# ADC_4CH.net
KiCad netlist of a schematic drawn in Altium Designer
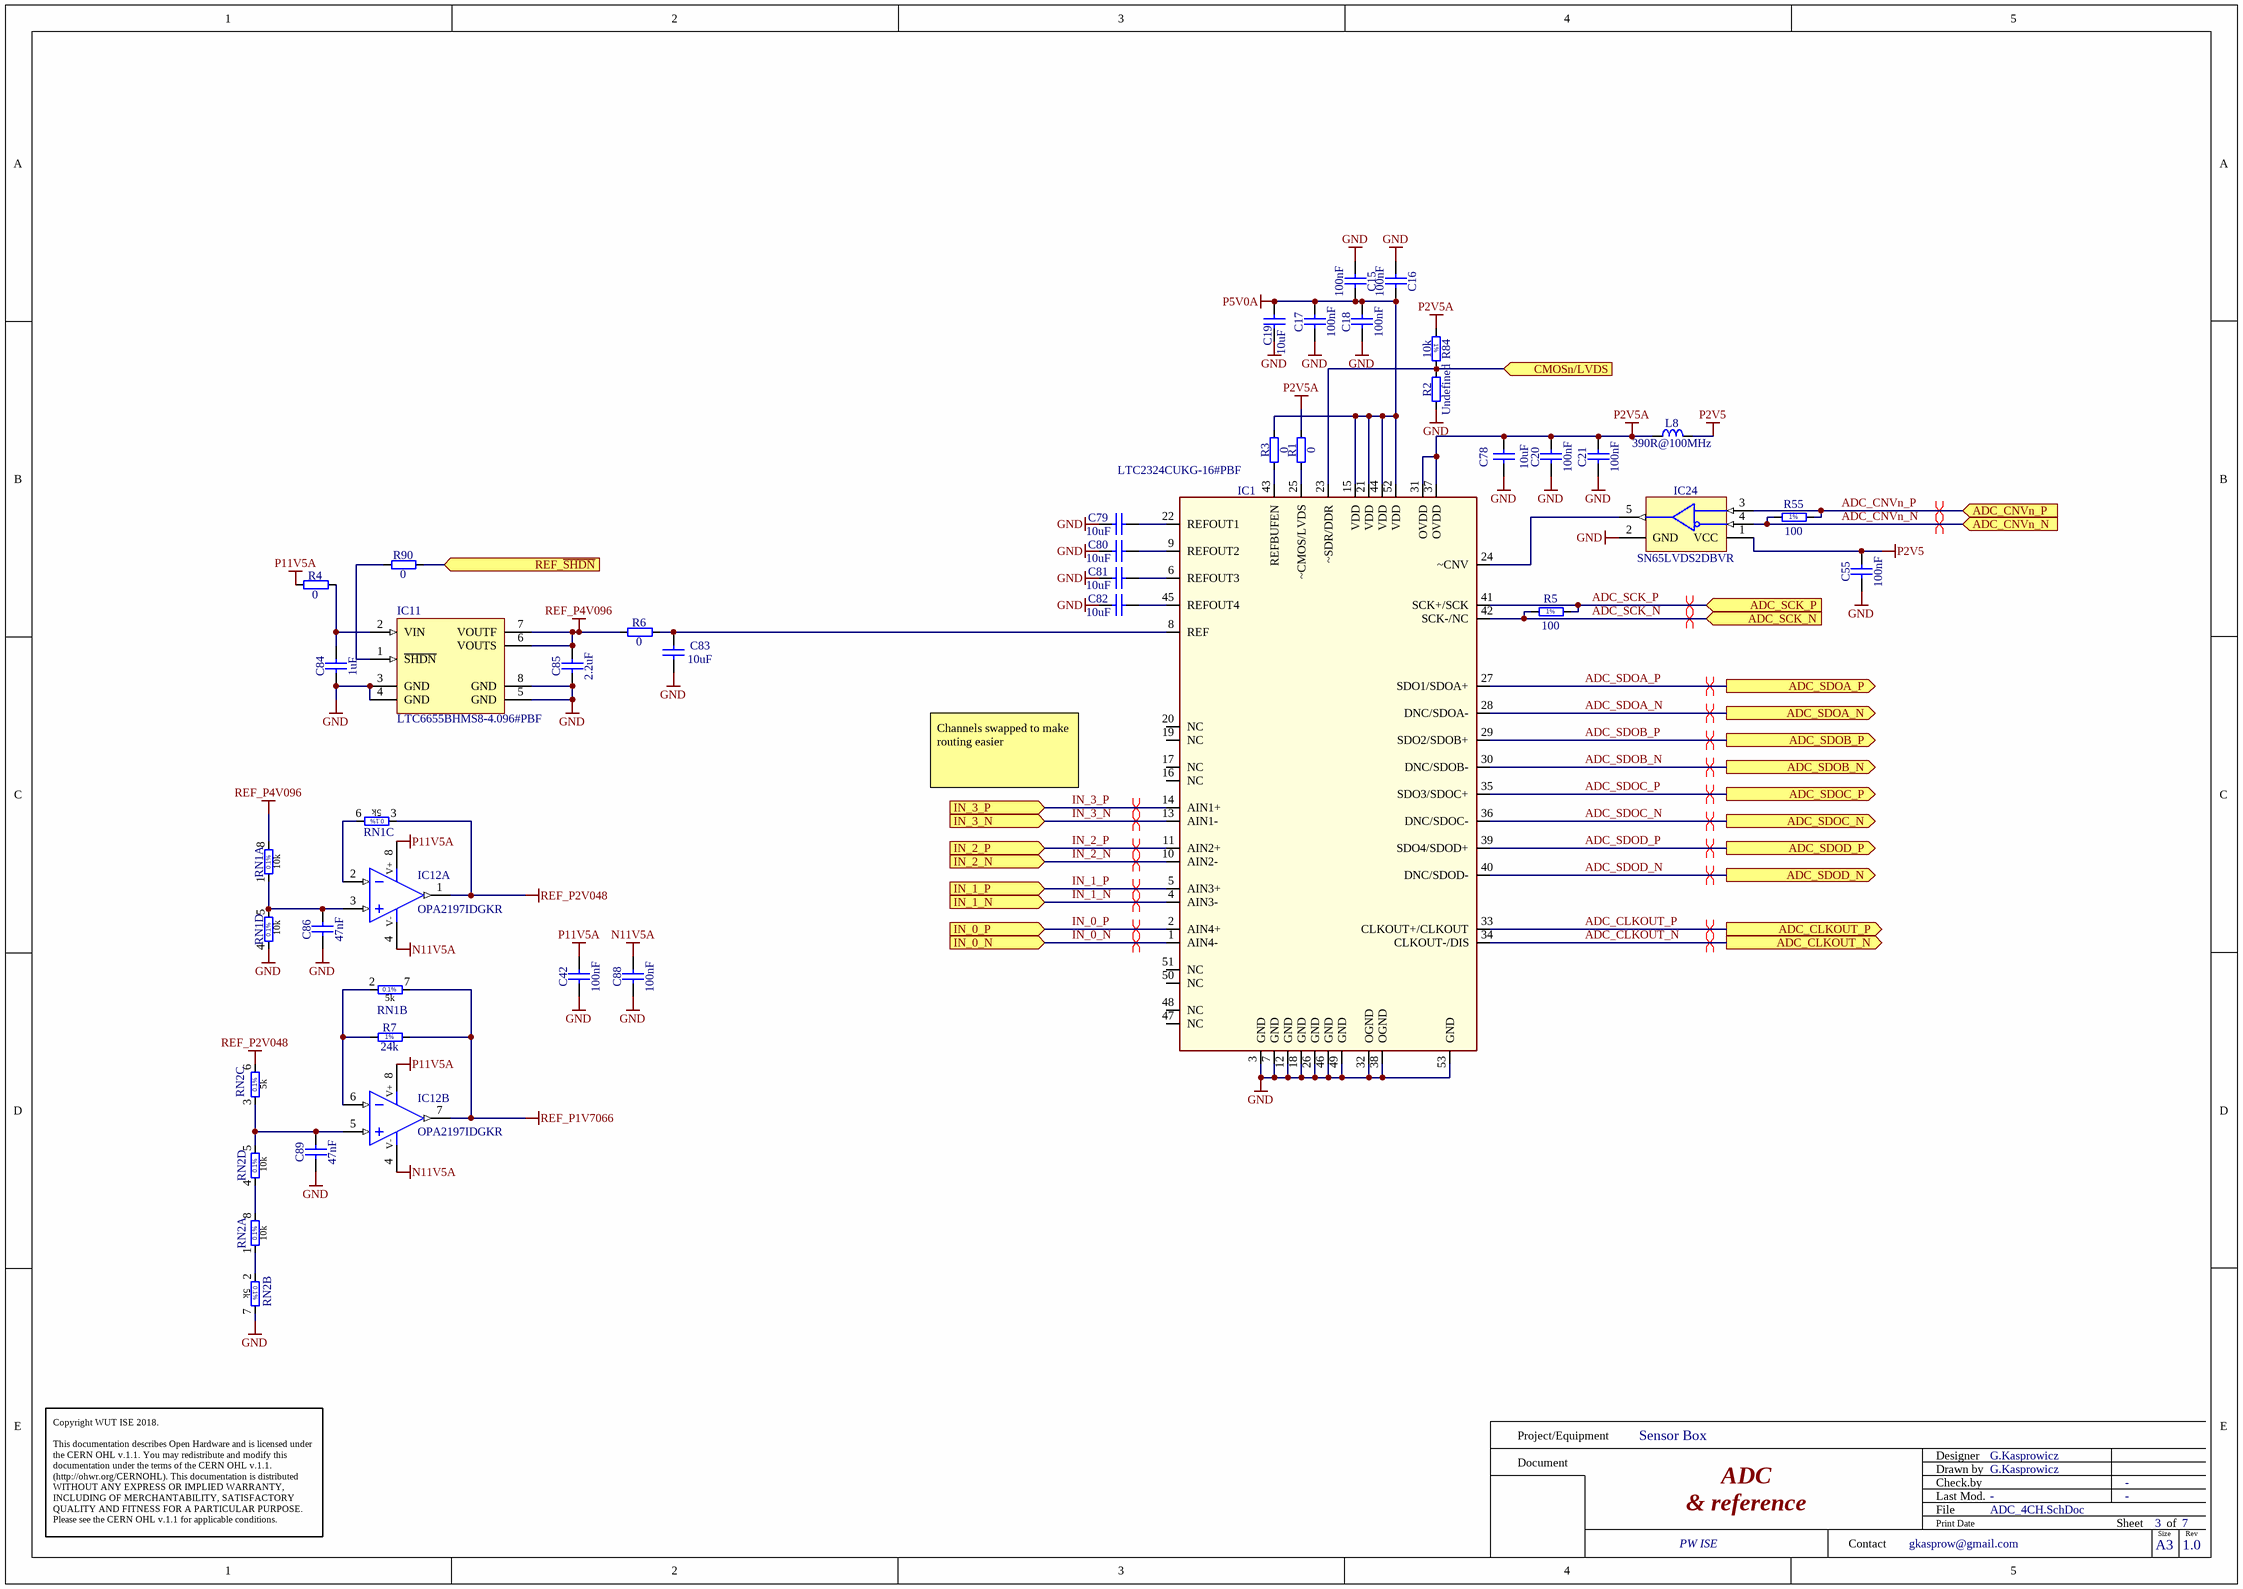
[diagram p0: ADC_4CH.SchDoc]

(export (version "E")
  (design (tool "Eeschema 10.0.6"))
  (components
    (comp (ref "C15")
      (value "100nF")
      (footprint "CAPC1608X87N")
      (description "Non-polarised capacitor")
      (fields
        (field (name "PART NUMBER") "CC0603_100NF_50V_10%_X7R")
        (field (name "VOLTAGE") "50V")
        (field (name "AUTHOR") "CERN DEM JLC")
      )
      (libsource (lib "Capacitors") (part "Capacitor - non polarized"))
    )
    (comp (ref "C16")
      (value "100nF")
      (footprint "CAPC1608X87N")
      (description "Non-polarised capacitor")
      (fields
        (field (name "PART NUMBER") "CC0603_100NF_50V_10%_X7R")
        (field (name "VOLTAGE") "50V")
        (field (name "AUTHOR") "CERN DEM JLC")
      )
      (libsource (lib "Capacitors") (part "Capacitor - non polarized"))
    )
    (comp (ref "C17")
      (value "100nF")
      (footprint "CAPC1608X87N")
      (description "Non-polarised capacitor")
      (fields
        (field (name "PART NUMBER") "CC0603_100NF_50V_10%_X7R")
        (field (name "VOLTAGE") "50V")
        (field (name "AUTHOR") "CERN DEM JLC")
      )
      (libsource (lib "Capacitors") (part "Capacitor - non polarized"))
    )
    (comp (ref "C18")
      (value "100nF")
      (footprint "CAPC1608X87N")
      (description "Non-polarised capacitor")
      (fields
        (field (name "PART NUMBER") "CC0603_100NF_50V_10%_X7R")
        (field (name "VOLTAGE") "50V")
        (field (name "AUTHOR") "CERN DEM JLC")
      )
      (libsource (lib "Capacitors") (part "Capacitor - non polarized"))
    )
    (comp (ref "C19")
      (value "10uF")
      (footprint "CAPC2012X95N")
      (description "Non-polarised capacitor")
      (fields
        (field (name "PART NUMBER") "CC0805_10UF_25V_10%_X5R")
        (field (name "VOLTAGE") "25V")
        (field (name "AUTHOR") "CERN DEM JLC")
      )
      (libsource (lib "Capacitors") (part "Capacitor - non polarized"))
    )
    (comp (ref "C20")
      (value "100nF")
      (footprint "CAPC1608X87N")
      (description "Non-polarised capacitor")
      (fields
        (field (name "PART NUMBER") "CC0603_100NF_50V_10%_X7R")
        (field (name "VOLTAGE") "50V")
        (field (name "AUTHOR") "CERN DEM JLC")
      )
      (libsource (lib "Capacitors") (part "Capacitor - non polarized"))
    )
    (comp (ref "C21")
      (value "100nF")
      (footprint "CAPC1608X87N")
      (description "Non-polarised capacitor")
      (fields
        (field (name "PART NUMBER") "CC0603_100NF_50V_10%_X7R")
        (field (name "VOLTAGE") "50V")
        (field (name "AUTHOR") "CERN DEM JLC")
      )
      (libsource (lib "Capacitors") (part "Capacitor - non polarized"))
    )
    (comp (ref "C42")
      (value "100nF")
      (footprint "CAPC1005X55N")
      (description "Non-polarised capacitor")
      (fields
        (field (name "PART NUMBER") "CC0402_100NF_16V_10%_X5R")
        (field (name "VOLTAGE") "16V")
        (field (name "AUTHOR") "CERN DEM JLC")
      )
      (libsource (lib "Capacitors") (part "Capacitor - non polarized"))
    )
    (comp (ref "C55")
      (value "100nF")
      (footprint "CAPC1608X87N")
      (description "Non-polarised capacitor")
      (fields
        (field (name "PART NUMBER") "CC0603_100NF_50V_10%_X7R")
        (field (name "VOLTAGE") "50V")
        (field (name "AUTHOR") "CERN DEM JLC")
      )
      (libsource (lib "Capacitors") (part "Capacitor - non polarized"))
    )
    (comp (ref "C78")
      (value "10uF")
      (footprint "CAPC2012X95N")
      (description "Non-polarised capacitor")
      (fields
        (field (name "PART NUMBER") "CC0805_10UF_25V_10%_X5R")
        (field (name "VOLTAGE") "25V")
        (field (name "AUTHOR") "CERN DEM JLC")
      )
      (libsource (lib "Capacitors") (part "Capacitor - non polarized"))
    )
    (comp (ref "C79")
      (value "10uF")
      (footprint "CAPC2012X95N")
      (description "Non-polarised capacitor")
      (fields
        (field (name "PART NUMBER") "CC0805_10UF_25V_10%_X5R")
        (field (name "VOLTAGE") "25V")
        (field (name "AUTHOR") "CERN DEM JLC")
      )
      (libsource (lib "Capacitors") (part "Capacitor - non polarized"))
    )
    (comp (ref "C80")
      (value "10uF")
      (footprint "CAPC2012X95N")
      (description "Non-polarised capacitor")
      (fields
        (field (name "PART NUMBER") "CC0805_10UF_25V_10%_X5R")
        (field (name "VOLTAGE") "25V")
        (field (name "AUTHOR") "CERN DEM JLC")
      )
      (libsource (lib "Capacitors") (part "Capacitor - non polarized"))
    )
    (comp (ref "C81")
      (value "10uF")
      (footprint "CAPC2012X95N")
      (description "Non-polarised capacitor")
      (fields
        (field (name "PART NUMBER") "CC0805_10UF_25V_10%_X5R")
        (field (name "VOLTAGE") "25V")
        (field (name "AUTHOR") "CERN DEM JLC")
      )
      (libsource (lib "Capacitors") (part "Capacitor - non polarized"))
    )
    (comp (ref "C82")
      (value "10uF")
      (footprint "CAPC2012X95N")
      (description "Non-polarised capacitor")
      (fields
        (field (name "PART NUMBER") "CC0805_10UF_25V_10%_X5R")
        (field (name "VOLTAGE") "25V")
        (field (name "AUTHOR") "CERN DEM JLC")
      )
      (libsource (lib "Capacitors") (part "Capacitor - non polarized"))
    )
    (comp (ref "C83")
      (value "10uF")
      (footprint "CAPC2012X95N")
      (description "Non-polarised capacitor")
      (fields
        (field (name "PART NUMBER") "CC0805_10UF_25V_10%_X5R")
        (field (name "VOLTAGE") "25V")
        (field (name "AUTHOR") "CERN DEM JLC")
      )
      (libsource (lib "Capacitors") (part "Capacitor - non polarized"))
    )
    (comp (ref "C84")
      (value "1uF")
      (footprint "CAPC1608X87N")
      (description "Non-polarised capacitor")
      (fields
        (field (name "PART NUMBER") "CC0603_1UF_25V_10%_X7R")
        (field (name "VOLTAGE") "25V")
        (field (name "AUTHOR") "CERN DEM JLC")
      )
      (libsource (lib "Capacitors") (part "Capacitor - non polarized"))
    )
    (comp (ref "C85")
      (value "2.2uF")
      (footprint "CAPC1608X87N")
      (description "Non-polarised capacitor")
      (fields
        (field (name "PART NUMBER") "CC0603_2.2UF_16V_10%_X5R")
        (field (name "VOLTAGE") "16V")
        (field (name "AUTHOR") "CERN DEM JLC")
      )
      (libsource (lib "Capacitors") (part "Capacitor - non polarized"))
    )
    (comp (ref "C86")
      (value "47nF")
      (footprint "CAPC2012X135N")
      (description "Non-polarised capacitor")
      (fields
        (field (name "PART NUMBER") "CC0805_47NF_25V_5%_C0G")
        (field (name "VOLTAGE") "25V")
        (field (name "AUTHOR") "CERN DEM JLC")
      )
      (libsource (lib "Capacitors") (part "Capacitor - non polarized"))
    )
    (comp (ref "C88")
      (value "100nF")
      (footprint "CAPC1005X55N")
      (description "Non-polarised capacitor")
      (fields
        (field (name "PART NUMBER") "CC0402_100NF_16V_10%_X5R")
        (field (name "VOLTAGE") "16V")
        (field (name "AUTHOR") "CERN DEM JLC")
      )
      (libsource (lib "Capacitors") (part "Capacitor - non polarized"))
    )
    (comp (ref "C89")
      (value "47nF")
      (footprint "CAPC2012X135N")
      (description "Non-polarised capacitor")
      (fields
        (field (name "PART NUMBER") "CC0805_47NF_25V_5%_C0G")
        (field (name "VOLTAGE") "25V")
        (field (name "AUTHOR") "CERN DEM JLC")
      )
      (libsource (lib "Capacitors") (part "Capacitor - non polarized"))
    )
    (comp (ref "IC1")
      (value "LTC2324CUKG-16#PBF")
      (footprint "QFN50P700X800X80_HS-53M")
      (description "Quad, 16-Bit, 2Msps/Ch  Simultaneous Sampling ADC")
      (fields (field (name "MANUFACTURER") "LINEAR TECHNOLOGY") (field (name "AUTHOR") "GK"))
      (libsource (lib "LIBRARY_SCH") (part "ADC_LTC2324CUKG-16"))
    )
    (comp (ref "IC11")
      (value "LTC6655BHMS8-4.096#PBF")
      (footprint "SOP65P490X110-8N")
      (description "0.25ppm Noise, Low Drift Precision Buffered Voltage Reference")
      (fields (field (name "MANUFACTURER") "LINEAR TECHNOLOGY") (field (name "AUTHOR") "GK"))
      (libsource (lib "LIBRARY_SCH") (part "REF_LTC6655"))
    )
    (comp (ref "IC12")
      (value "OPA2197IDGKR")
      (footprint "SOP65P490X110-8N")
      (description "36-V, Precision, Rail-to-Rail Input Output, Low Offset Voltage Op Amp 8-VSSOP")
      (fields (field (name "MANUFACTURER") "TEXAS INSTRUMENTS") (field (name "AUTHOR") "GK"))
      (libsource (lib "LIBRARY_SCH") (part "OA_OPA2197IDGKR"))
    )
    (comp (ref "IC24")
      (value "SN65LVDS2DBVR")
      (footprint "SOT95P280X145-5N")
      (description "High-Speed Differential Line Receiver")
      (fields (field (name "MANUFACTURER") "TEXAS INSTRUMENTS") (field (name "AUTHOR") "CERN DEM JLC"))
      (libsource (lib "ICs And Semiconductors") (part "SN65LVDS2DBV"))
    )
    (comp (ref "L8")
      (value "390R@100MHz")
      (footprint "INDC1608X95N")
      (description "Inductor")
      (fields
        (field (name "PART NUMBER") "IND0603_TDK_MPZ1608R391A")
        (field (name "POWER") "1.2A")
        (field (name "AUTHOR") "CERN DEM JLC")
      )
      (libsource (lib "Inductors & Transformers") (part "Inductor"))
    )
    (comp (ref "R1")
      (value "0")
      (footprint "RESC1005X40N")
      (description "Resistor")
      (fields
        (field (name "PART NUMBER") "R0402_0R_JUMPER")
        (field (name "MANUFACTURER") "GENERIC")
        (field (name "AUTHOR") "CERN DEM JLC")
      )
      (libsource (lib "Resistors") (part "Resistor"))
    )
    (comp (ref "R2")
      (value "Undefined")
      (footprint "RESC1005X40N")
      (description "Resistor")
      (fields (field (name "PART NUMBER") "R0402_NO-VALUE") (field (name "AUTHOR") "CERN DEM JLC"))
      (libsource (lib "Resistors") (part "Resistor"))
    )
    (comp (ref "R3")
      (value "0")
      (footprint "RESC1005X40N")
      (description "Resistor")
      (fields
        (field (name "PART NUMBER") "R0402_0R_JUMPER")
        (field (name "MANUFACTURER") "GENERIC")
        (field (name "AUTHOR") "CERN DEM JLC")
      )
      (libsource (lib "Resistors") (part "Resistor"))
    )
    (comp (ref "R4")
      (value "0")
      (footprint "RESC1005X40N")
      (description "Resistor")
      (fields
        (field (name "PART NUMBER") "R0402_0R_JUMPER")
        (field (name "MANUFACTURER") "GENERIC")
        (field (name "AUTHOR") "CERN DEM JLC")
      )
      (libsource (lib "Resistors") (part "Resistor"))
    )
    (comp (ref "R5")
      (value "100")
      (footprint "RESC1005X40N")
      (description "Resistor - 1%")
      (fields
        (field (name "PART NUMBER") "R0402_100R_1%_0.1W_100PPM")
        (field (name "POWER") "0.1W")
        (field (name "AUTHOR") "CERN DEM JLC")
      )
      (libsource (lib "Resistors") (part "Resistor - 1%"))
    )
    (comp (ref "R6")
      (value "0")
      (footprint "RESC1005X40N")
      (description "Resistor")
      (fields
        (field (name "PART NUMBER") "R0402_0R_JUMPER")
        (field (name "MANUFACTURER") "GENERIC")
        (field (name "AUTHOR") "CERN DEM JLC")
      )
      (libsource (lib "Resistors") (part "Resistor"))
    )
    (comp (ref "R7")
      (value "24k")
      (footprint "RESC1608X55N")
      (description "Resistor - 1%")
      (fields
        (field (name "PART NUMBER") "R0603_24K_1%_0.1W_100PPM")
        (field (name "POWER") "0.1W")
        (field (name "AUTHOR") "CERN DEM JLC")
      )
      (libsource (lib "Resistors") (part "Resistor - 1%"))
    )
    (comp (ref "R55")
      (value "100")
      (footprint "RESC1005X40N")
      (description "Resistor - 1%")
      (fields
        (field (name "PART NUMBER") "R0402_100R_1%_0.1W_100PPM")
        (field (name "POWER") "0.1W")
        (field (name "AUTHOR") "CERN DEM JLC")
      )
      (libsource (lib "Resistors") (part "Resistor - 1%"))
    )
    (comp (ref "R84")
      (value "10k")
      (footprint "RESC1005X40N")
      (description "Resistor - 1%")
      (fields
        (field (name "PART NUMBER") "R0402_10K_1%_0.0625W_100PPM")
        (field (name "POWER") "0.0625W")
        (field (name "AUTHOR") "CERN DEM JLC")
      )
      (libsource (lib "Resistors") (part "Resistor - 1%"))
    )
    (comp (ref "R90")
      (value "0")
      (footprint "RESC1005X40N")
      (description "Resistor")
      (fields
        (field (name "PART NUMBER") "R0402_0R_JUMPER")
        (field (name "MANUFACTURER") "GENERIC")
        (field (name "AUTHOR") "CERN DEM JLC")
      )
      (libsource (lib "Resistors") (part "Resistor"))
    )
    (comp (ref "RN1")
      (value "10k 5K 5K 10K")
      (footprint "SOIC127P600X175-8N")
      (description "DIL8 Resistor Network 4 Resistors 10k-5k-5k-10k 0.1%")
      (fields
        (field (name "PART NUMBER") "RN_10K_5K_VISHAY_AORN2-1AT3")
        (field (name "POWER") "4x0.1W")
        (field (name "AUTHOR") "CERN DEM JLC")
      )
      (libsource (lib "Resistors") (part "RN DIL8_4xR_10k-5k-5k-10k_0.1%"))
    )
    (comp (ref "RN2")
      (value "10k 5K 5K 10K")
      (footprint "SOIC127P600X175-8N")
      (description "DIL8 Resistor Network 4 Resistors 10k-5k-5k-10k 0.1%")
      (fields
        (field (name "PART NUMBER") "RN_10K_5K_VISHAY_AORN2-1AT3")
        (field (name "POWER") "4x0.1W")
        (field (name "AUTHOR") "CERN DEM JLC")
      )
      (libsource (lib "Resistors") (part "RN DIL8_4xR_10k-5k-5k-10k_0.1%"))
    )
  )
  (nets
    (net (code "1") (name "/ADC_CLKOUT_N") (class "Default")
      (node (ref "IC1") (pin "34") (pinfunction "CLKOUT-/DIS_34") (pintype "passive"))
    )
    (net (code "2") (name "/ADC_CLKOUT_P") (class "Default")
      (node (ref "IC1") (pin "33") (pinfunction "CLKOUT+/CLKOUT_33") (pintype "passive"))
    )
    (net (code "3") (name "/ADC_CNVn_N") (class "Default")
      (node (ref "IC24") (pin "4") (pinfunction "B_4") (pintype "input"))
      (node (ref "R55") (pin "1") (pinfunction "1_1") (pintype "passive"))
    )
    (net (code "4") (name "/ADC_CNVn_P") (class "Default")
      (node (ref "IC24") (pin "3") (pinfunction "A_3") (pintype "input"))
      (node (ref "R55") (pin "2") (pinfunction "2_2") (pintype "passive"))
    )
    (net (code "5") (name "/ADC_SCK_N") (class "Default")
      (node (ref "IC1") (pin "42") (pinfunction "SCK-/NC_42") (pintype "passive"))
      (node (ref "R5") (pin "1") (pinfunction "1_1") (pintype "passive"))
    )
    (net (code "6") (name "/ADC_SCK_P") (class "Default")
      (node (ref "IC1") (pin "41") (pinfunction "SCK+/SCK_41") (pintype "passive"))
      (node (ref "R5") (pin "2") (pinfunction "2_2") (pintype "passive"))
    )
    (net (code "7") (name "/ADC_SDOA_N") (class "Default")
      (node (ref "IC1") (pin "28") (pinfunction "DNC/SDOA-_28") (pintype "passive"))
    )
    (net (code "8") (name "/ADC_SDOA_P") (class "Default")
      (node (ref "IC1") (pin "27") (pinfunction "SDO1/SDOA+_27") (pintype "passive"))
    )
    (net (code "9") (name "/ADC_SDOB_N") (class "Default")
      (node (ref "IC1") (pin "30") (pinfunction "DNC/SDOB-_30") (pintype "passive"))
    )
    (net (code "10") (name "/ADC_SDOB_P") (class "Default")
      (node (ref "IC1") (pin "29") (pinfunction "SDO2/SDOB+_29") (pintype "passive"))
    )
    (net (code "11") (name "/ADC_SDOC_N") (class "Default")
      (node (ref "IC1") (pin "36") (pinfunction "DNC/SDOC-_36") (pintype "passive"))
    )
    (net (code "12") (name "/ADC_SDOC_P") (class "Default")
      (node (ref "IC1") (pin "35") (pinfunction "SDO3/SDOC+_35") (pintype "passive"))
    )
    (net (code "13") (name "/ADC_SDOD_N") (class "Default")
      (node (ref "IC1") (pin "40") (pinfunction "DNC/SDOD-_40") (pintype "passive"))
    )
    (net (code "14") (name "/ADC_SDOD_P") (class "Default")
      (node (ref "IC1") (pin "39") (pinfunction "SDO4/SDOD+_39") (pintype "passive"))
    )
    (net (code "15") (name "/CMOSn{slash}LVDS") (class "Default")
      (node (ref "IC1") (pin "23") (pinfunction "~SDR/DDR_23") (pintype "passive"))
      (node (ref "R2") (pin "2") (pinfunction "2_2") (pintype "passive"))
      (node (ref "R84") (pin "2") (pinfunction "2_2") (pintype "passive"))
    )
    (net (code "16") (name "/IN_0_N") (class "Default")
      (node (ref "IC1") (pin "1") (pinfunction "AIN4-_1") (pintype "passive"))
    )
    (net (code "17") (name "/IN_0_P") (class "Default")
      (node (ref "IC1") (pin "2") (pinfunction "AIN4+_2") (pintype "passive"))
    )
    (net (code "18") (name "/IN_1_N") (class "Default")
      (node (ref "IC1") (pin "4") (pinfunction "AIN3-_4") (pintype "passive"))
    )
    (net (code "19") (name "/IN_1_P") (class "Default")
      (node (ref "IC1") (pin "5") (pinfunction "AIN3+_5") (pintype "passive"))
    )
    (net (code "20") (name "/IN_2_N") (class "Default")
      (node (ref "IC1") (pin "10") (pinfunction "AIN2-_10") (pintype "passive"))
    )
    (net (code "21") (name "/IN_2_P") (class "Default")
      (node (ref "IC1") (pin "11") (pinfunction "AIN2+_11") (pintype "passive"))
    )
    (net (code "22") (name "/IN_3_N") (class "Default")
      (node (ref "IC1") (pin "13") (pinfunction "AIN1-_13") (pintype "passive"))
    )
    (net (code "23") (name "/IN_3_P") (class "Default")
      (node (ref "IC1") (pin "14") (pinfunction "AIN1+_14") (pintype "passive"))
    )
    (net (code "24") (name "/REF_~{SHDN}") (class "Default")
      (node (ref "R90") (pin "2") (pinfunction "2_2") (pintype "passive"))
    )
    (net (code "25") (name "GND") (class "Default")
      (node (ref "C15") (pin "1") (pinfunction "1_1") (pintype "passive"))
      (node (ref "C16") (pin "1") (pinfunction "1_1") (pintype "passive"))
      (node (ref "C17") (pin "1") (pinfunction "1_1") (pintype "passive"))
      (node (ref "C18") (pin "1") (pinfunction "1_1") (pintype "passive"))
      (node (ref "C19") (pin "1") (pinfunction "1_1") (pintype "passive"))
      (node (ref "C20") (pin "1") (pinfunction "1_1") (pintype "passive"))
      (node (ref "C21") (pin "1") (pinfunction "1_1") (pintype "passive"))
      (node (ref "C42") (pin "1") (pinfunction "1_1") (pintype "passive"))
      (node (ref "C55") (pin "1") (pinfunction "1_1") (pintype "passive"))
      (node (ref "C78") (pin "1") (pinfunction "1_1") (pintype "passive"))
      (node (ref "C79") (pin "1") (pinfunction "1_1") (pintype "passive"))
      (node (ref "C80") (pin "1") (pinfunction "1_1") (pintype "passive"))
      (node (ref "C81") (pin "1") (pinfunction "1_1") (pintype "passive"))
      (node (ref "C82") (pin "1") (pinfunction "1_1") (pintype "passive"))
      (node (ref "C83") (pin "1") (pinfunction "1_1") (pintype "passive"))
      (node (ref "C84") (pin "1") (pinfunction "1_1") (pintype "passive"))
      (node (ref "C85") (pin "1") (pinfunction "1_1") (pintype "passive"))
      (node (ref "C86") (pin "1") (pinfunction "1_1") (pintype "passive"))
      (node (ref "C88") (pin "1") (pinfunction "1_1") (pintype "passive"))
      (node (ref "C89") (pin "1") (pinfunction "1_1") (pintype "passive"))
      (node (ref "IC1") (pin "12") (pinfunction "GND_12") (pintype "passive"))
      (node (ref "IC1") (pin "18") (pinfunction "GND_18") (pintype "passive"))
      (node (ref "IC1") (pin "26") (pinfunction "GND_26") (pintype "passive"))
      (node (ref "IC1") (pin "3") (pinfunction "GND_3") (pintype "passive"))
      (node (ref "IC1") (pin "32") (pinfunction "OGND_32") (pintype "passive"))
      (node (ref "IC1") (pin "38") (pinfunction "OGND_38") (pintype "passive"))
      (node (ref "IC1") (pin "46") (pinfunction "GND_46") (pintype "passive"))
      (node (ref "IC1") (pin "49") (pinfunction "GND_49") (pintype "passive"))
      (node (ref "IC1") (pin "53") (pinfunction "GND_53") (pintype "passive"))
      (node (ref "IC1") (pin "7") (pinfunction "GND_7") (pintype "passive"))
      (node (ref "IC11") (pin "3") (pinfunction "GND_3") (pintype "power_in"))
      (node (ref "IC11") (pin "4") (pinfunction "GND_4") (pintype "power_in"))
      (node (ref "IC11") (pin "5") (pinfunction "GND_5") (pintype "power_in"))
      (node (ref "IC11") (pin "8") (pinfunction "GND_8") (pintype "power_in"))
      (node (ref "IC24") (pin "2") (pinfunction "GND_2") (pintype "power_in"))
      (node (ref "R2") (pin "1") (pinfunction "1_1") (pintype "passive"))
      (node (ref "RN1") (pin "4") (pinfunction "4_4") (pintype "passive"))
      (node (ref "RN2") (pin "7") (pinfunction "7_7") (pintype "passive"))
    )
    (net (code "26") (name "N11V5A") (class "Default")
      (node (ref "C88") (pin "2") (pinfunction "2_2") (pintype "passive"))
      (node (ref "IC12") (pin "4") (pinfunction "V-_4") (pintype "power_in"))
    )
    (net (code "27") (name "Net-(IC1-REF)") (class "Default")
      (node (ref "C83") (pin "2") (pinfunction "2_2") (pintype "passive"))
      (node (ref "IC1") (pin "8") (pinfunction "REF_8") (pintype "passive"))
      (node (ref "R6") (pin "2") (pinfunction "2_2") (pintype "passive"))
    )
    (net (code "28") (name "Net-(IC1-REFBUFEN)") (class "Default")
      (node (ref "IC1") (pin "43") (pinfunction "REFBUFEN_43") (pintype "passive"))
      (node (ref "R3") (pin "1") (pinfunction "1_1") (pintype "passive"))
    )
    (net (code "29") (name "Net-(IC1-REFOUT1)") (class "Default")
      (node (ref "C79") (pin "2") (pinfunction "2_2") (pintype "passive"))
      (node (ref "IC1") (pin "22") (pinfunction "REFOUT1_22") (pintype "passive"))
    )
    (net (code "30") (name "Net-(IC1-REFOUT2)") (class "Default")
      (node (ref "C80") (pin "2") (pinfunction "2_2") (pintype "passive"))
      (node (ref "IC1") (pin "9") (pinfunction "REFOUT2_9") (pintype "passive"))
    )
    (net (code "31") (name "Net-(IC1-REFOUT3)") (class "Default")
      (node (ref "C81") (pin "2") (pinfunction "2_2") (pintype "passive"))
      (node (ref "IC1") (pin "6") (pinfunction "REFOUT3_6") (pintype "passive"))
    )
    (net (code "32") (name "Net-(IC1-REFOUT4)") (class "Default")
      (node (ref "C82") (pin "2") (pinfunction "2_2") (pintype "passive"))
      (node (ref "IC1") (pin "45") (pinfunction "REFOUT4_45") (pintype "passive"))
    )
    (net (code "33") (name "Net-(IC1-~CMOS{slash}LVDS)") (class "Default")
      (node (ref "IC1") (pin "25") (pinfunction "~CMOS/LVDS_25") (pintype "passive"))
      (node (ref "R1") (pin "1") (pinfunction "1_1") (pintype "passive"))
    )
    (net (code "34") (name "Net-(IC1-~CNV)") (class "Default")
      (node (ref "IC1") (pin "24") (pinfunction "~CNV_24") (pintype "passive"))
      (node (ref "IC24") (pin "5") (pinfunction "R_5") (pintype "output"))
    )
    (net (code "35") (name "Net-(IC11-VIN)") (class "Default")
      (node (ref "C84") (pin "2") (pinfunction "2_2") (pintype "passive"))
      (node (ref "IC11") (pin "2") (pinfunction "VIN_2") (pintype "input"))
      (node (ref "R4") (pin "2") (pinfunction "2_2") (pintype "passive"))
    )
    (net (code "36") (name "Net-(IC11-~{SHDN})") (class "Default")
      (node (ref "IC11") (pin "1") (pinfunction "~{SHDN}_1") (pintype "input"))
      (node (ref "R90") (pin "1") (pinfunction "1_1") (pintype "passive"))
    )
    (net (code "37") (name "Net-(IC12A-IN+)") (class "Default")
      (node (ref "C86") (pin "2") (pinfunction "2_2") (pintype "passive"))
      (node (ref "IC12") (pin "3") (pinfunction "IN+_3") (pintype "input"))
      (node (ref "RN1") (pin "1") (pinfunction "1_1") (pintype "passive"))
      (node (ref "RN1") (pin "5") (pinfunction "5_5") (pintype "passive"))
    )
    (net (code "38") (name "Net-(IC12A-IN-)") (class "Default")
      (node (ref "IC12") (pin "2") (pinfunction "IN-_2") (pintype "input"))
      (node (ref "RN1") (pin "6") (pinfunction "6_6") (pintype "passive"))
    )
    (net (code "39") (name "Net-(IC12B-IN+)") (class "Default")
      (node (ref "C89") (pin "2") (pinfunction "2_2") (pintype "passive"))
      (node (ref "IC12") (pin "5") (pinfunction "IN+_5") (pintype "input"))
      (node (ref "RN2") (pin "3") (pinfunction "3_3") (pintype "passive"))
      (node (ref "RN2") (pin "5") (pinfunction "5_5") (pintype "passive"))
    )
    (net (code "40") (name "Net-(IC12B-IN-)") (class "Default")
      (node (ref "IC12") (pin "6") (pinfunction "IN-_6") (pintype "input"))
      (node (ref "R7") (pin "1") (pinfunction "1_1") (pintype "passive"))
      (node (ref "RN1") (pin "2") (pinfunction "2_2") (pintype "passive"))
    )
    (net (code "41") (name "Net-(RN2-Pad1)") (class "Default")
      (node (ref "RN2") (pin "1") (pinfunction "1_1") (pintype "passive"))
      (node (ref "RN2") (pin "2") (pinfunction "2_2") (pintype "passive"))
    )
    (net (code "42") (name "Net-(RN2-Pad4)") (class "Default")
      (node (ref "RN2") (pin "4") (pinfunction "4_4") (pintype "passive"))
      (node (ref "RN2") (pin "8") (pinfunction "8_8") (pintype "passive"))
    )
    (net (code "43") (name "P2V5") (class "Default")
      (node (ref "C55") (pin "2") (pinfunction "2_2") (pintype "passive"))
      (node (ref "IC24") (pin "1") (pinfunction "VCC_1") (pintype "power_in"))
      (node (ref "L8") (pin "2") (pinfunction "2_2") (pintype "passive"))
    )
    (net (code "44") (name "P2V5A") (class "Default")
      (node (ref "C20") (pin "2") (pinfunction "2_2") (pintype "passive"))
      (node (ref "C21") (pin "2") (pinfunction "2_2") (pintype "passive"))
      (node (ref "C78") (pin "2") (pinfunction "2_2") (pintype "passive"))
      (node (ref "IC1") (pin "31") (pinfunction "OVDD_31") (pintype "passive"))
      (node (ref "IC1") (pin "37") (pinfunction "OVDD_37") (pintype "passive"))
      (node (ref "L8") (pin "1") (pinfunction "1_1") (pintype "passive"))
      (node (ref "R1") (pin "2") (pinfunction "2_2") (pintype "passive"))
      (node (ref "R84") (pin "1") (pinfunction "1_1") (pintype "passive"))
    )
    (net (code "45") (name "P5V0A") (class "Default")
      (node (ref "C15") (pin "2") (pinfunction "2_2") (pintype "passive"))
      (node (ref "C16") (pin "2") (pinfunction "2_2") (pintype "passive"))
      (node (ref "C17") (pin "2") (pinfunction "2_2") (pintype "passive"))
      (node (ref "C18") (pin "2") (pinfunction "2_2") (pintype "passive"))
      (node (ref "C19") (pin "2") (pinfunction "2_2") (pintype "passive"))
      (node (ref "IC1") (pin "15") (pinfunction "VDD_15") (pintype "passive"))
      (node (ref "IC1") (pin "21") (pinfunction "VDD_21") (pintype "passive"))
      (node (ref "IC1") (pin "44") (pinfunction "VDD_44") (pintype "passive"))
      (node (ref "IC1") (pin "52") (pinfunction "VDD_52") (pintype "passive"))
      (node (ref "R3") (pin "2") (pinfunction "2_2") (pintype "passive"))
    )
    (net (code "46") (name "P11V5A") (class "Default")
      (node (ref "C42") (pin "2") (pinfunction "2_2") (pintype "passive"))
      (node (ref "IC12") (pin "8") (pinfunction "V+_8") (pintype "power_in"))
      (node (ref "R4") (pin "1") (pinfunction "1_1") (pintype "passive"))
    )
    (net (code "47") (name "REF_P1V7066") (class "Default")
      (node (ref "IC12") (pin "7") (pinfunction "OUT_7") (pintype "output"))
      (node (ref "R7") (pin "2") (pinfunction "2_2") (pintype "passive"))
      (node (ref "RN1") (pin "7") (pinfunction "7_7") (pintype "passive"))
    )
    (net (code "48") (name "REF_P2V048") (class "Default")
      (node (ref "IC12") (pin "1") (pinfunction "OUT_1") (pintype "output"))
      (node (ref "RN1") (pin "3") (pinfunction "3_3") (pintype "passive"))
      (node (ref "RN2") (pin "6") (pinfunction "6_6") (pintype "passive"))
    )
    (net (code "49") (name "REF_P4V096") (class "Default")
      (node (ref "C85") (pin "2") (pinfunction "2_2") (pintype "passive"))
      (node (ref "IC11") (pin "6") (pinfunction "VOUTS_6") (pintype "power_in"))
      (node (ref "IC11") (pin "7") (pinfunction "VOUTF_7") (pintype "power_in"))
      (node (ref "R6") (pin "1") (pinfunction "1_1") (pintype "passive"))
      (node (ref "RN1") (pin "8") (pinfunction "8_8") (pintype "passive"))
    )
    (net (code "50") (name "unconnected-(IC1-NC-Pad16)") (class "Default")
      (node (ref "IC1") (pin "16") (pinfunction "NC_16") (pintype "passive"))
    )
    (net (code "51") (name "unconnected-(IC1-NC-Pad17)") (class "Default")
      (node (ref "IC1") (pin "17") (pinfunction "NC_17") (pintype "passive"))
    )
    (net (code "52") (name "unconnected-(IC1-NC-Pad19)") (class "Default")
      (node (ref "IC1") (pin "19") (pinfunction "NC_19") (pintype "passive"))
    )
    (net (code "53") (name "unconnected-(IC1-NC-Pad20)") (class "Default")
      (node (ref "IC1") (pin "20") (pinfunction "NC_20") (pintype "passive"))
    )
    (net (code "54") (name "unconnected-(IC1-NC-Pad47)") (class "Default")
      (node (ref "IC1") (pin "47") (pinfunction "NC_47") (pintype "passive"))
    )
    (net (code "55") (name "unconnected-(IC1-NC-Pad48)") (class "Default")
      (node (ref "IC1") (pin "48") (pinfunction "NC_48") (pintype "passive"))
    )
    (net (code "56") (name "unconnected-(IC1-NC-Pad50)") (class "Default")
      (node (ref "IC1") (pin "50") (pinfunction "NC_50") (pintype "passive"))
    )
    (net (code "57") (name "unconnected-(IC1-NC-Pad51)") (class "Default")
      (node (ref "IC1") (pin "51") (pinfunction "NC_51") (pintype "passive"))
    )
  )
)
